# clh100-001RevA.net
KiCad netlist of a schematic drawn in EAGLE
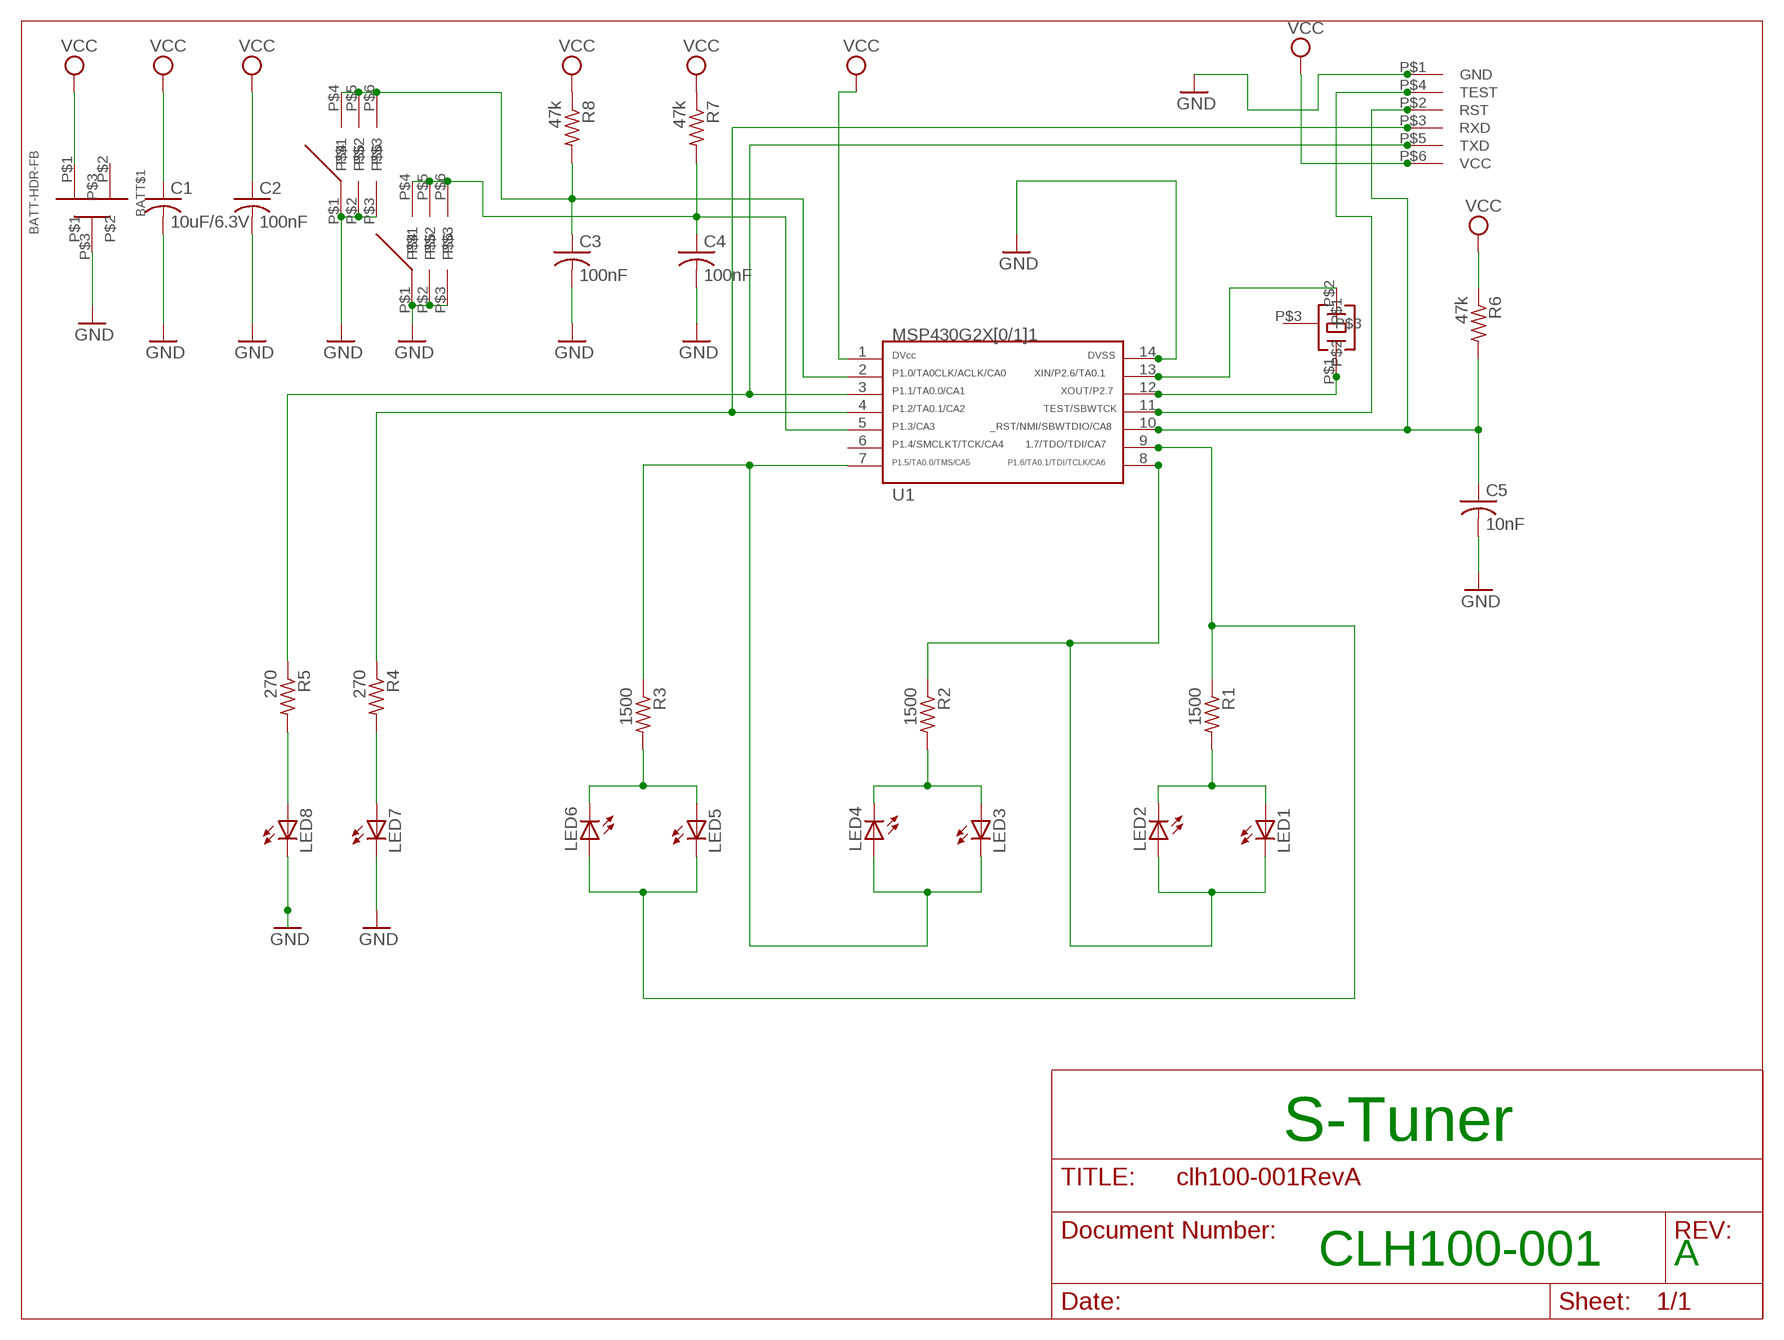
[diagram p0: schematic, sheet 1]

(export (version "E")
  (design (tool "Eeschema 10.0.6"))
  (components
    (comp (ref "BATT1")
      (value "BATT1")
      (footprint "eagle-import:BATT-HDR-FB")
      (libsource (lib "eagle-import") (part "BATT-HDR-FB"))
    )
    (comp (ref "C1")
      (value "10uF/6.3V")
      (footprint "eagle-import:C1206K")
      (libsource (lib "eagle-import") (part "C-USC1206K"))
    )
    (comp (ref "C2")
      (value "100nF")
      (footprint "eagle-import:C0603")
      (libsource (lib "eagle-import") (part "resistor_C-USC0603"))
    )
    (comp (ref "C3")
      (value "100nF")
      (footprint "eagle-import:C0603")
      (libsource (lib "eagle-import") (part "resistor_C-USC0603"))
    )
    (comp (ref "C4")
      (value "100nF")
      (footprint "eagle-import:C0603")
      (libsource (lib "eagle-import") (part "resistor_C-USC0603"))
    )
    (comp (ref "C5")
      (value "10nF")
      (footprint "eagle-import:C0603")
      (libsource (lib "eagle-import") (part "resistor_C-USC0603"))
    )
    (comp (ref "LED1")
      (value "LEDSML0805")
      (footprint "eagle-import:SML0805")
      (libsource (lib "eagle-import") (part "LEDSML0805"))
    )
    (comp (ref "LED2")
      (value "LEDSML0805")
      (footprint "eagle-import:SML0805")
      (libsource (lib "eagle-import") (part "LEDSML0805"))
    )
    (comp (ref "LED3")
      (value "LEDSML0805")
      (footprint "eagle-import:SML0805")
      (libsource (lib "eagle-import") (part "LEDSML0805"))
    )
    (comp (ref "LED4")
      (value "LEDSML0805")
      (footprint "eagle-import:SML0805")
      (libsource (lib "eagle-import") (part "LEDSML0805"))
    )
    (comp (ref "LED5")
      (value "LEDSML0805")
      (footprint "eagle-import:SML0805")
      (libsource (lib "eagle-import") (part "LEDSML0805"))
    )
    (comp (ref "LED6")
      (value "LEDSML0805")
      (footprint "eagle-import:SML0805")
      (libsource (lib "eagle-import") (part "LEDSML0805"))
    )
    (comp (ref "LED7")
      (value "LED3MM")
      (footprint "eagle-import:LED3MM")
      (libsource (lib "eagle-import") (part "LED3MM"))
    )
    (comp (ref "LED8")
      (value "LED3MM")
      (footprint "eagle-import:LED3MM")
      (libsource (lib "eagle-import") (part "LED3MM"))
    )
    (comp (ref "R1")
      (value "1500")
      (footprint "eagle-import:R0603")
      (libsource (lib "eagle-import") (part "R-US_R0603"))
    )
    (comp (ref "R2")
      (value "1500")
      (footprint "eagle-import:R0603")
      (libsource (lib "eagle-import") (part "R-US_R0603"))
    )
    (comp (ref "R3")
      (value "1500")
      (footprint "eagle-import:R0603")
      (libsource (lib "eagle-import") (part "R-US_R0603"))
    )
    (comp (ref "R4")
      (value "270")
      (footprint "eagle-import:R0603")
      (libsource (lib "eagle-import") (part "R-US_R0603"))
    )
    (comp (ref "R5")
      (value "270")
      (footprint "eagle-import:R0603")
      (libsource (lib "eagle-import") (part "R-US_R0603"))
    )
    (comp (ref "R6")
      (value "47k")
      (footprint "eagle-import:R0603")
      (libsource (lib "eagle-import") (part "R-US_R0603"))
    )
    (comp (ref "R7")
      (value "47k")
      (footprint "eagle-import:R0603")
      (libsource (lib "eagle-import") (part "R-US_R0603"))
    )
    (comp (ref "R8")
      (value "47k")
      (footprint "eagle-import:R0603")
      (libsource (lib "eagle-import") (part "R-US_R0603"))
    )
    (comp (ref "SW1")
      (value "POLYCASE_FINGER_TRACE")
      (footprint "eagle-import:POLYCASE_FINGER_TRACE")
      (libsource (lib "eagle-import") (part "POLYCASE_FINGER_TRACE"))
    )
    (comp (ref "SW2")
      (value "POLYCASE_FINGER_TRACE")
      (footprint "eagle-import:POLYCASE_FINGER_TRACE")
      (libsource (lib "eagle-import") (part "POLYCASE_FINGER_TRACE"))
    )
    (comp (ref "U$3")
      (value "PROGRAMMING_HEADER")
      (footprint "eagle-import:PROGRAMMING_HEADER")
      (libsource (lib "eagle-import") (part "PROGRAMMING_HEADER"))
    )
    (comp (ref "U1")
      (value "G2X[0/1]1---PW14")
      (footprint "eagle-import:PW14")
      (libsource (lib "eagle-import") (part "G2X[0/1]1---PW14"))
    )
    (comp (ref "U2")
      (value "MICROCRYSTAL_32K")
      (footprint "eagle-import:MICROCRYSTAL_32K")
      (libsource (lib "eagle-import") (part "MICROCRYSTAL_32K"))
    )
  )
  (nets
    (net (code "1") (name "GND") (class "Default")
      (node (ref "BATT1") (pin "P$3") (pinfunction "P$3_P$3") (pintype "bidirectional"))
      (node (ref "C1") (pin "2") (pinfunction "2_2") (pintype "passive"))
      (node (ref "C2") (pin "2") (pinfunction "2_2") (pintype "passive"))
      (node (ref "C3") (pin "2") (pinfunction "2_2") (pintype "passive"))
      (node (ref "C4") (pin "2") (pinfunction "2_2") (pintype "passive"))
      (node (ref "C5") (pin "2") (pinfunction "2_2") (pintype "passive"))
      (node (ref "LED7") (pin "K") (pinfunction "C_K") (pintype "passive"))
      (node (ref "LED8") (pin "K") (pinfunction "C_K") (pintype "passive"))
      (node (ref "SW1") (pin "P$1") (pinfunction "P$1_P$1") (pintype "bidirectional"))
      (node (ref "SW1") (pin "P$2") (pinfunction "P$2_P$2") (pintype "bidirectional"))
      (node (ref "SW1") (pin "P$3") (pinfunction "P$3_P$3") (pintype "bidirectional"))
      (node (ref "SW2") (pin "P$1") (pinfunction "P$1_P$1") (pintype "bidirectional"))
      (node (ref "SW2") (pin "P$2") (pinfunction "P$2_P$2") (pintype "bidirectional"))
      (node (ref "SW2") (pin "P$3") (pinfunction "P$3_P$3") (pintype "bidirectional"))
      (node (ref "U$3") (pin "P$1") (pinfunction "GND_P$1") (pintype "bidirectional"))
      (node (ref "U1") (pin "14") (pinfunction "14_14") (pintype "bidirectional"))
    )
    (net (code "2") (name "Net-(C3-Pad1)") (class "Default")
      (node (ref "C3") (pin "1") (pinfunction "1_1") (pintype "passive"))
      (node (ref "R8") (pin "2") (pinfunction "2_2") (pintype "passive"))
      (node (ref "SW1") (pin "P$4") (pinfunction "P$4_P$4") (pintype "bidirectional"))
      (node (ref "SW1") (pin "P$5") (pinfunction "P$5_P$5") (pintype "bidirectional"))
      (node (ref "SW1") (pin "P$6") (pinfunction "P$6_P$6") (pintype "bidirectional"))
      (node (ref "U1") (pin "2") (pinfunction "2_2") (pintype "bidirectional"))
    )
    (net (code "3") (name "Net-(C4-Pad1)") (class "Default")
      (node (ref "C4") (pin "1") (pinfunction "1_1") (pintype "passive"))
      (node (ref "R7") (pin "2") (pinfunction "2_2") (pintype "passive"))
      (node (ref "SW2") (pin "P$4") (pinfunction "P$4_P$4") (pintype "bidirectional"))
      (node (ref "SW2") (pin "P$5") (pinfunction "P$5_P$5") (pintype "bidirectional"))
      (node (ref "SW2") (pin "P$6") (pinfunction "P$6_P$6") (pintype "bidirectional"))
      (node (ref "U1") (pin "5") (pinfunction "5_5") (pintype "bidirectional"))
    )
    (net (code "4") (name "Net-(LED1-PadA)") (class "Default")
      (node (ref "LED1") (pin "A") (pinfunction "A_A") (pintype "passive"))
      (node (ref "LED2") (pin "C") (pinfunction "C_C") (pintype "passive"))
      (node (ref "R1") (pin "2") (pinfunction "2_2") (pintype "passive"))
    )
    (net (code "5") (name "Net-(LED1-PadC)") (class "Default")
      (node (ref "LED1") (pin "C") (pinfunction "C_C") (pintype "passive"))
      (node (ref "LED2") (pin "A") (pinfunction "A_A") (pintype "passive"))
      (node (ref "R2") (pin "1") (pinfunction "1_1") (pintype "passive"))
      (node (ref "U1") (pin "8") (pinfunction "8_8") (pintype "bidirectional"))
    )
    (net (code "6") (name "Net-(LED3-PadA)") (class "Default")
      (node (ref "LED3") (pin "A") (pinfunction "A_A") (pintype "passive"))
      (node (ref "LED4") (pin "C") (pinfunction "C_C") (pintype "passive"))
      (node (ref "R2") (pin "2") (pinfunction "2_2") (pintype "passive"))
    )
    (net (code "7") (name "Net-(LED3-PadC)") (class "Default")
      (node (ref "LED3") (pin "C") (pinfunction "C_C") (pintype "passive"))
      (node (ref "LED4") (pin "A") (pinfunction "A_A") (pintype "passive"))
      (node (ref "R3") (pin "1") (pinfunction "1_1") (pintype "passive"))
      (node (ref "U1") (pin "7") (pinfunction "7_7") (pintype "bidirectional"))
    )
    (net (code "8") (name "Net-(LED5-PadA)") (class "Default")
      (node (ref "LED5") (pin "A") (pinfunction "A_A") (pintype "passive"))
      (node (ref "LED6") (pin "C") (pinfunction "C_C") (pintype "passive"))
      (node (ref "R3") (pin "2") (pinfunction "2_2") (pintype "passive"))
    )
    (net (code "9") (name "Net-(LED5-PadC)") (class "Default")
      (node (ref "LED5") (pin "C") (pinfunction "C_C") (pintype "passive"))
      (node (ref "LED6") (pin "A") (pinfunction "A_A") (pintype "passive"))
      (node (ref "R1") (pin "1") (pinfunction "1_1") (pintype "passive"))
      (node (ref "U1") (pin "9") (pinfunction "9_9") (pintype "bidirectional"))
    )
    (net (code "10") (name "Net-(LED7-PadA)") (class "Default")
      (node (ref "LED7") (pin "A") (pinfunction "A_A") (pintype "passive"))
      (node (ref "R4") (pin "2") (pinfunction "2_2") (pintype "passive"))
    )
    (net (code "11") (name "Net-(LED8-PadA)") (class "Default")
      (node (ref "LED8") (pin "A") (pinfunction "A_A") (pintype "passive"))
      (node (ref "R5") (pin "2") (pinfunction "2_2") (pintype "passive"))
    )
    (net (code "12") (name "Net-(U$3-RST)") (class "Default")
      (node (ref "C5") (pin "1") (pinfunction "1_1") (pintype "passive"))
      (node (ref "R6") (pin "2") (pinfunction "2_2") (pintype "passive"))
      (node (ref "U$3") (pin "P$2") (pinfunction "RST_P$2") (pintype "bidirectional"))
      (node (ref "U1") (pin "10") (pinfunction "10_10") (pintype "bidirectional"))
    )
    (net (code "13") (name "Net-(U$3-RXD)") (class "Default")
      (node (ref "R4") (pin "1") (pinfunction "1_1") (pintype "passive"))
      (node (ref "U$3") (pin "P$3") (pinfunction "RXD_P$3") (pintype "bidirectional"))
      (node (ref "U1") (pin "4") (pinfunction "4_4") (pintype "bidirectional"))
    )
    (net (code "14") (name "Net-(U$3-TEST)") (class "Default")
      (node (ref "U$3") (pin "P$4") (pinfunction "TEST_P$4") (pintype "bidirectional"))
      (node (ref "U1") (pin "11") (pinfunction "11_11") (pintype "bidirectional"))
    )
    (net (code "15") (name "Net-(U$3-TXD)") (class "Default")
      (node (ref "R5") (pin "1") (pinfunction "1_1") (pintype "passive"))
      (node (ref "U$3") (pin "P$5") (pinfunction "TXD_P$5") (pintype "bidirectional"))
      (node (ref "U1") (pin "3") (pinfunction "3_3") (pintype "bidirectional"))
    )
    (net (code "16") (name "Net-(U1-Pad12)") (class "Default")
      (node (ref "U1") (pin "12") (pinfunction "12_12") (pintype "bidirectional"))
      (node (ref "U2") (pin "P$1") (pinfunction "P$1_P$1") (pintype "bidirectional"))
    )
    (net (code "17") (name "Net-(U1-Pad13)") (class "Default")
      (node (ref "U1") (pin "13") (pinfunction "13_13") (pintype "bidirectional"))
      (node (ref "U2") (pin "P$2") (pinfunction "P$2_P$2") (pintype "bidirectional"))
    )
    (net (code "18") (name "VCC") (class "Default")
      (node (ref "BATT1") (pin "P$1") (pinfunction "P$1_P$1") (pintype "bidirectional"))
      (node (ref "C1") (pin "1") (pinfunction "1_1") (pintype "passive"))
      (node (ref "C2") (pin "1") (pinfunction "1_1") (pintype "passive"))
      (node (ref "R6") (pin "1") (pinfunction "1_1") (pintype "passive"))
      (node (ref "R7") (pin "1") (pinfunction "1_1") (pintype "passive"))
      (node (ref "R8") (pin "1") (pinfunction "1_1") (pintype "passive"))
      (node (ref "U$3") (pin "P$6") (pinfunction "VCC_P$6") (pintype "bidirectional"))
      (node (ref "U1") (pin "1") (pinfunction "1_1") (pintype "bidirectional"))
    )
    (net (code "19") (name "unconnected-(BATT1-PadP$2)") (class "Default")
      (node (ref "BATT1") (pin "P$2") (pinfunction "P$2_P$2") (pintype "bidirectional"))
    )
    (net (code "20") (name "unconnected-(U1-Pad6)") (class "Default")
      (node (ref "U1") (pin "6") (pinfunction "6_6") (pintype "bidirectional"))
    )
    (net (code "21") (name "unconnected-(U2-PadP$3)") (class "Default")
      (node (ref "U2") (pin "P$3") (pinfunction "P$3_P$3") (pintype "bidirectional"))
    )
  )
)
